# M621X.net
KiCad netlist of a schematic drawn in EAGLE
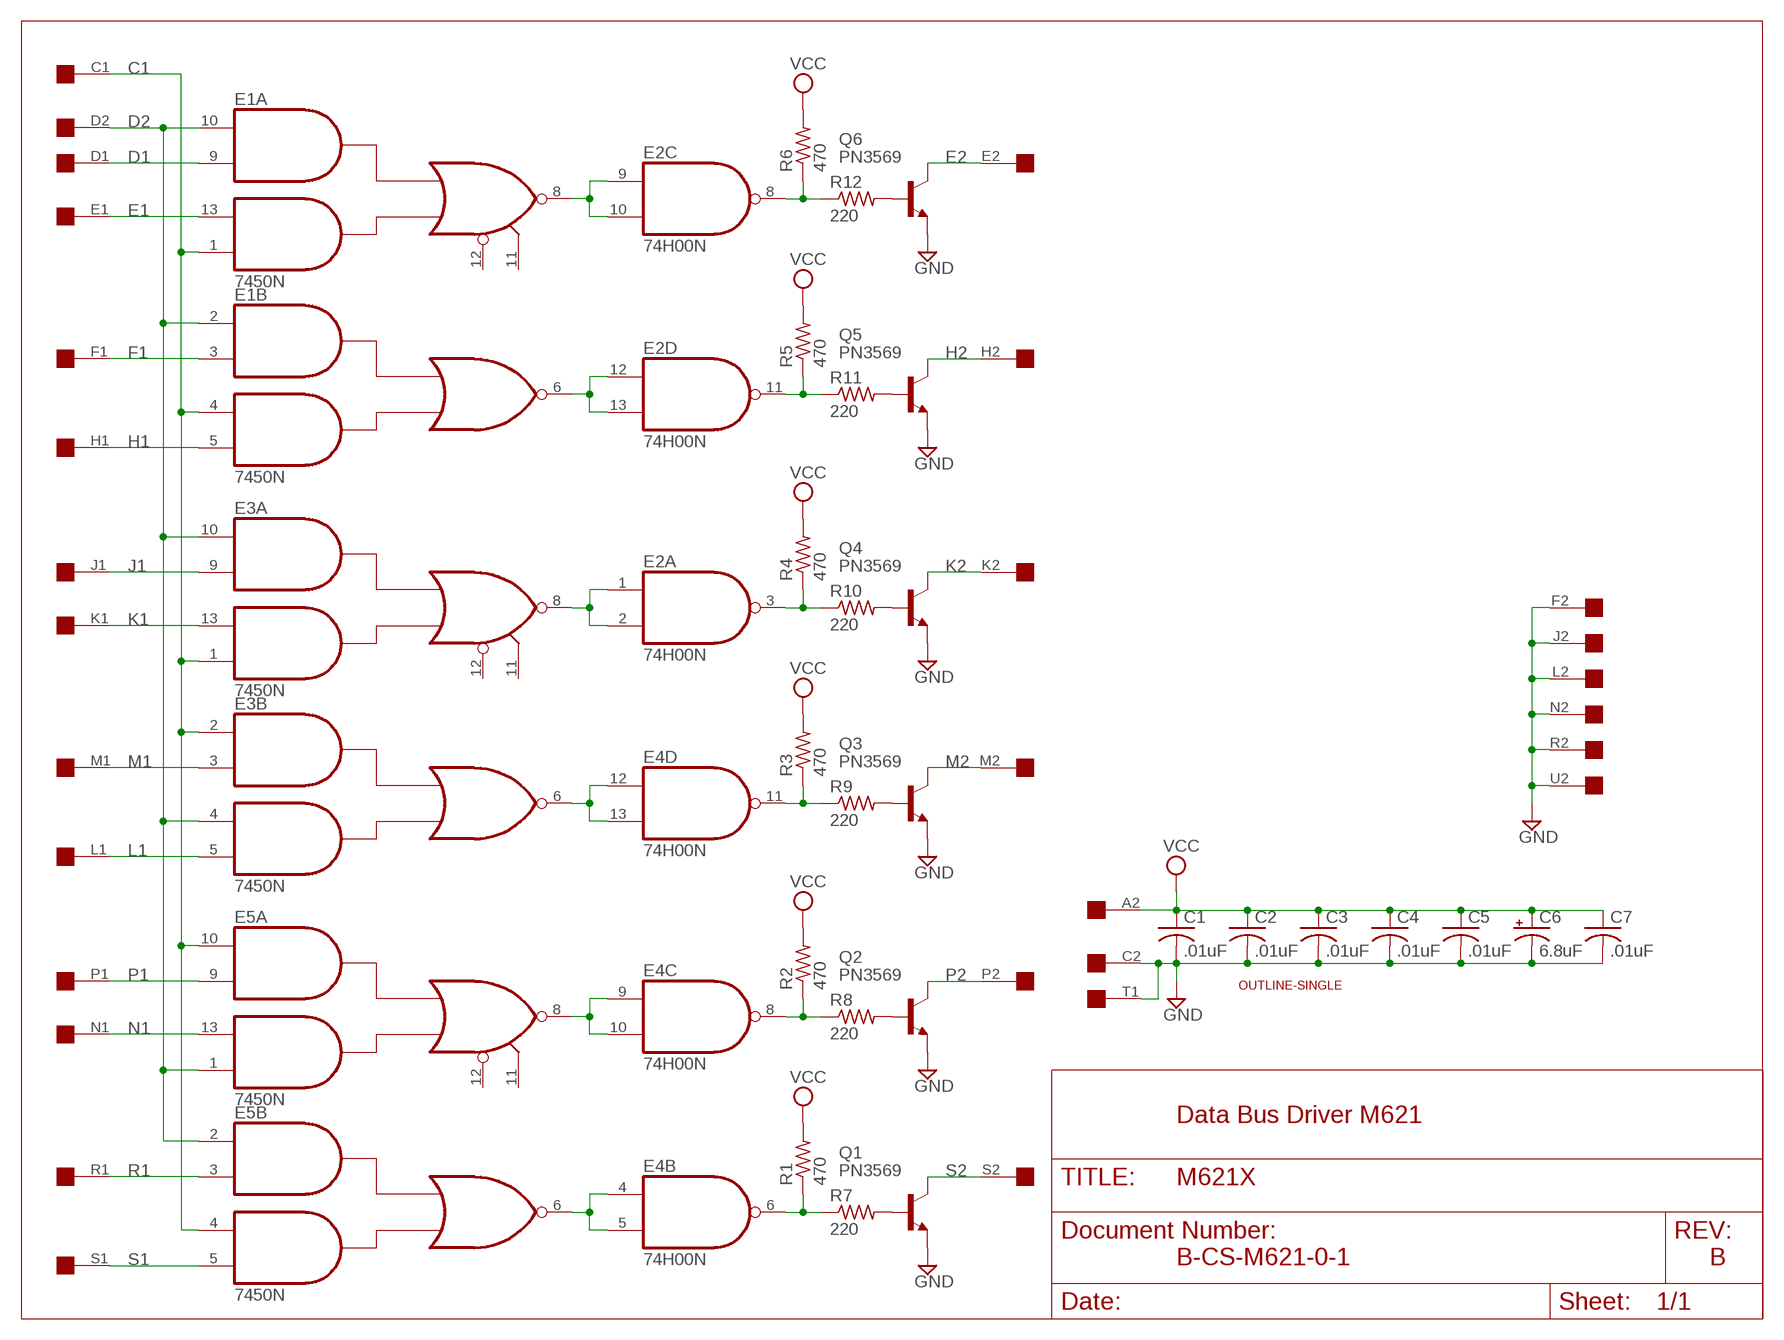
[diagram p0: schematic, sheet 1]

(export (version "E")
  (design (tool "Eeschema 10.0.6"))
  (components
    (comp (ref "C1")
      (value ".01uF")
      (footprint "eagle-import:C063-025X075")
      (libsource (lib "eagle-import") (part "C-US"))
    )
    (comp (ref "C2")
      (value ".01uF")
      (footprint "eagle-import:C063-025X075")
      (libsource (lib "eagle-import") (part "C-US"))
    )
    (comp (ref "C3")
      (value ".01uF")
      (footprint "eagle-import:C063-025X075")
      (libsource (lib "eagle-import") (part "C-US"))
    )
    (comp (ref "C4")
      (value ".01uF")
      (footprint "eagle-import:C063-025X075")
      (libsource (lib "eagle-import") (part "C-US"))
    )
    (comp (ref "C5")
      (value ".01uF")
      (footprint "eagle-import:C063-025X075")
      (libsource (lib "eagle-import") (part "C-US"))
    )
    (comp (ref "C6")
      (value "6.8uF")
      (footprint "eagle-import:E15-5")
      (libsource (lib "eagle-import") (part "CPOL-USE15-5AXIAL"))
    )
    (comp (ref "C7")
      (value ".01uF")
      (footprint "eagle-import:C063-025X075")
      (libsource (lib "eagle-import") (part "C-US"))
    )
    (comp (ref "E1")
      (value "7450N")
      (footprint "eagle-import:DIL14")
      (libsource (lib "eagle-import") (part "7450N"))
    )
    (comp (ref "E2")
      (value "74H00N")
      (footprint "eagle-import:DIL14")
      (libsource (lib "eagle-import") (part "7400NS"))
    )
    (comp (ref "E3")
      (value "7450N")
      (footprint "eagle-import:DIL14")
      (libsource (lib "eagle-import") (part "7450N"))
    )
    (comp (ref "E4")
      (value "74H00N")
      (footprint "eagle-import:DIL14")
      (libsource (lib "eagle-import") (part "7400NS"))
    )
    (comp (ref "E5")
      (value "7450N")
      (footprint "eagle-import:DIL14")
      (libsource (lib "eagle-import") (part "7450N"))
    )
    (comp (ref "Q1")
      (value "PN3569")
      (footprint "eagle-import:TO5")
      (libsource (lib "eagle-import") (part "-NPN-TO5"))
    )
    (comp (ref "Q2")
      (value "PN3569")
      (footprint "eagle-import:TO5")
      (libsource (lib "eagle-import") (part "-NPN-TO5"))
    )
    (comp (ref "Q3")
      (value "PN3569")
      (footprint "eagle-import:TO5")
      (libsource (lib "eagle-import") (part "-NPN-TO5"))
    )
    (comp (ref "Q4")
      (value "PN3569")
      (footprint "eagle-import:TO5")
      (libsource (lib "eagle-import") (part "-NPN-TO5"))
    )
    (comp (ref "Q5")
      (value "PN3569")
      (footprint "eagle-import:TO5")
      (libsource (lib "eagle-import") (part "-NPN-TO5"))
    )
    (comp (ref "Q6")
      (value "PN3569")
      (footprint "eagle-import:TO5")
      (libsource (lib "eagle-import") (part "-NPN-TO5"))
    )
    (comp (ref "R1")
      (value "470")
      (footprint "eagle-import:0207_10")
      (libsource (lib "eagle-import") (part "R-US_0207/10"))
    )
    (comp (ref "R2")
      (value "470")
      (footprint "eagle-import:0207_10")
      (libsource (lib "eagle-import") (part "R-US_0207/10"))
    )
    (comp (ref "R3")
      (value "470")
      (footprint "eagle-import:0207_10")
      (libsource (lib "eagle-import") (part "R-US_0207/10"))
    )
    (comp (ref "R4")
      (value "470")
      (footprint "eagle-import:0207_10")
      (libsource (lib "eagle-import") (part "R-US_0207/10"))
    )
    (comp (ref "R5")
      (value "470")
      (footprint "eagle-import:0207_10")
      (libsource (lib "eagle-import") (part "R-US_0207/10"))
    )
    (comp (ref "R6")
      (value "470")
      (footprint "eagle-import:0207_10")
      (libsource (lib "eagle-import") (part "R-US_0207/10"))
    )
    (comp (ref "R7")
      (value "220")
      (footprint "eagle-import:0207_10")
      (libsource (lib "eagle-import") (part "R-US_0207/10"))
    )
    (comp (ref "R8")
      (value "220")
      (footprint "eagle-import:0207_10")
      (libsource (lib "eagle-import") (part "R-US_0207/10"))
    )
    (comp (ref "R9")
      (value "220")
      (footprint "eagle-import:0207_10")
      (libsource (lib "eagle-import") (part "R-US_0207/10"))
    )
    (comp (ref "R10")
      (value "220")
      (footprint "eagle-import:0207_10")
      (libsource (lib "eagle-import") (part "R-US_0207/10"))
    )
    (comp (ref "R11")
      (value "220")
      (footprint "eagle-import:0207_10")
      (libsource (lib "eagle-import") (part "R-US_0207/10"))
    )
    (comp (ref "R12")
      (value "220")
      (footprint "eagle-import:0207_10")
      (libsource (lib "eagle-import") (part "R-US_0207/10"))
    )
    (comp (ref "U$1")
      (value "OUTLINE-SINGLE")
      (footprint "eagle-import:SINGLE")
      (libsource (lib "eagle-import") (part "OUTLINE-SINGLE"))
    )
    (comp (ref "U$2")
      (value "edge")
      (footprint "eagle-import:EDGE-CON2")
      (libsource (lib "eagle-import") (part "SINGLE"))
    )
  )
  (nets
    (net (code "1") (name "/C1") (class "Default")
      (node (ref "E1") (pin "1") (pinfunction "I4_1") (pintype "input"))
      (node (ref "E1") (pin "4") (pinfunction "I3_4") (pintype "input"))
      (node (ref "E3") (pin "1") (pinfunction "I4_1") (pintype "input"))
      (node (ref "E3") (pin "2") (pinfunction "I1_2") (pintype "input"))
      (node (ref "E5") (pin "10") (pinfunction "I1_10") (pintype "input"))
      (node (ref "E5") (pin "4") (pinfunction "I3_4") (pintype "input"))
      (node (ref "U$2") (pin "C1") (pinfunction "1_C1") (pintype "bidirectional"))
    )
    (net (code "2") (name "/D1") (class "Default")
      (node (ref "E1") (pin "9") (pinfunction "I2_9") (pintype "input"))
      (node (ref "U$2") (pin "D1") (pinfunction "1_D1") (pintype "bidirectional"))
    )
    (net (code "3") (name "/D2") (class "Default")
      (node (ref "E1") (pin "10") (pinfunction "I1_10") (pintype "input"))
      (node (ref "E1") (pin "2") (pinfunction "I1_2") (pintype "input"))
      (node (ref "E3") (pin "10") (pinfunction "I1_10") (pintype "input"))
      (node (ref "E3") (pin "4") (pinfunction "I3_4") (pintype "input"))
      (node (ref "E5") (pin "1") (pinfunction "I4_1") (pintype "input"))
      (node (ref "E5") (pin "2") (pinfunction "I1_2") (pintype "input"))
      (node (ref "U$2") (pin "D2") (pinfunction "1_D2") (pintype "bidirectional"))
    )
    (net (code "4") (name "/E1") (class "Default")
      (node (ref "E1") (pin "13") (pinfunction "I3_13") (pintype "input"))
      (node (ref "U$2") (pin "E1") (pinfunction "1_E1") (pintype "bidirectional"))
    )
    (net (code "5") (name "/E2") (class "Default")
      (node (ref "Q6") (pin "3") (pinfunction "C_3") (pintype "passive"))
      (node (ref "U$2") (pin "E2") (pinfunction "1_E2") (pintype "bidirectional"))
    )
    (net (code "6") (name "/F1") (class "Default")
      (node (ref "E1") (pin "3") (pinfunction "I2_3") (pintype "input"))
      (node (ref "U$2") (pin "F1") (pinfunction "1_F1") (pintype "bidirectional"))
    )
    (net (code "7") (name "/H1") (class "Default")
      (node (ref "E1") (pin "5") (pinfunction "I4_5") (pintype "input"))
      (node (ref "U$2") (pin "H1") (pinfunction "1_H1") (pintype "bidirectional"))
    )
    (net (code "8") (name "/H2") (class "Default")
      (node (ref "Q5") (pin "3") (pinfunction "C_3") (pintype "passive"))
      (node (ref "U$2") (pin "H2") (pinfunction "1_H2") (pintype "bidirectional"))
    )
    (net (code "9") (name "/J1") (class "Default")
      (node (ref "E3") (pin "9") (pinfunction "I2_9") (pintype "input"))
      (node (ref "U$2") (pin "J1") (pinfunction "1_J1") (pintype "bidirectional"))
    )
    (net (code "10") (name "/K1") (class "Default")
      (node (ref "E3") (pin "13") (pinfunction "I3_13") (pintype "input"))
      (node (ref "U$2") (pin "K1") (pinfunction "1_K1") (pintype "bidirectional"))
    )
    (net (code "11") (name "/K2") (class "Default")
      (node (ref "Q4") (pin "3") (pinfunction "C_3") (pintype "passive"))
      (node (ref "U$2") (pin "K2") (pinfunction "1_K2") (pintype "bidirectional"))
    )
    (net (code "12") (name "/L1") (class "Default")
      (node (ref "E3") (pin "5") (pinfunction "I4_5") (pintype "input"))
      (node (ref "U$2") (pin "L1") (pinfunction "1_L1") (pintype "bidirectional"))
    )
    (net (code "13") (name "/M1") (class "Default")
      (node (ref "E3") (pin "3") (pinfunction "I2_3") (pintype "input"))
      (node (ref "U$2") (pin "M1") (pinfunction "1_M1") (pintype "bidirectional"))
    )
    (net (code "14") (name "/M2") (class "Default")
      (node (ref "Q3") (pin "3") (pinfunction "C_3") (pintype "passive"))
      (node (ref "U$2") (pin "M2") (pinfunction "1_M2") (pintype "bidirectional"))
    )
    (net (code "15") (name "/N1") (class "Default")
      (node (ref "E5") (pin "13") (pinfunction "I3_13") (pintype "input"))
      (node (ref "U$2") (pin "N1") (pinfunction "1_N1") (pintype "bidirectional"))
    )
    (net (code "16") (name "/P1") (class "Default")
      (node (ref "E5") (pin "9") (pinfunction "I2_9") (pintype "input"))
      (node (ref "U$2") (pin "P1") (pinfunction "1_P1") (pintype "bidirectional"))
    )
    (net (code "17") (name "/P2") (class "Default")
      (node (ref "Q2") (pin "3") (pinfunction "C_3") (pintype "passive"))
      (node (ref "U$2") (pin "P2") (pinfunction "1_P2") (pintype "bidirectional"))
    )
    (net (code "18") (name "/R1") (class "Default")
      (node (ref "E5") (pin "3") (pinfunction "I2_3") (pintype "input"))
      (node (ref "U$2") (pin "R1") (pinfunction "1_R1") (pintype "bidirectional"))
    )
    (net (code "19") (name "/S1") (class "Default")
      (node (ref "E5") (pin "5") (pinfunction "I4_5") (pintype "input"))
      (node (ref "U$2") (pin "S1") (pinfunction "1_S1") (pintype "bidirectional"))
    )
    (net (code "20") (name "/S2") (class "Default")
      (node (ref "Q1") (pin "3") (pinfunction "C_3") (pintype "passive"))
      (node (ref "U$2") (pin "S2") (pinfunction "1_S2") (pintype "bidirectional"))
    )
    (net (code "21") (name "GND") (class "Default")
      (node (ref "C1") (pin "2") (pinfunction "2_2") (pintype "passive"))
      (node (ref "C2") (pin "2") (pinfunction "2_2") (pintype "passive"))
      (node (ref "C3") (pin "2") (pinfunction "2_2") (pintype "passive"))
      (node (ref "C4") (pin "2") (pinfunction "2_2") (pintype "passive"))
      (node (ref "C5") (pin "2") (pinfunction "2_2") (pintype "passive"))
      (node (ref "C6") (pin "-") (pinfunction "-_-") (pintype "passive"))
      (node (ref "C7") (pin "2") (pinfunction "2_2") (pintype "passive"))
      (node (ref "Q1") (pin "1") (pinfunction "E_1") (pintype "passive"))
      (node (ref "Q2") (pin "1") (pinfunction "E_1") (pintype "passive"))
      (node (ref "Q3") (pin "1") (pinfunction "E_1") (pintype "passive"))
      (node (ref "Q4") (pin "1") (pinfunction "E_1") (pintype "passive"))
      (node (ref "Q5") (pin "1") (pinfunction "E_1") (pintype "passive"))
      (node (ref "Q6") (pin "1") (pinfunction "E_1") (pintype "passive"))
      (node (ref "U$2") (pin "C2") (pinfunction "1_C2") (pintype "bidirectional"))
      (node (ref "U$2") (pin "F2") (pinfunction "1_F2") (pintype "bidirectional"))
      (node (ref "U$2") (pin "J2") (pinfunction "1_J2") (pintype "bidirectional"))
      (node (ref "U$2") (pin "L2") (pinfunction "1_L2") (pintype "bidirectional"))
      (node (ref "U$2") (pin "N2") (pinfunction "1_N2") (pintype "bidirectional"))
      (node (ref "U$2") (pin "R2") (pinfunction "1_R2") (pintype "bidirectional"))
      (node (ref "U$2") (pin "T1") (pinfunction "1_T1") (pintype "bidirectional"))
      (node (ref "U$2") (pin "U2") (pinfunction "1_U2") (pintype "bidirectional"))
    )
    (net (code "22") (name "Net-(E1A-O)") (class "Default")
      (node (ref "E1") (pin "8") (pinfunction "O_8") (pintype "output"))
      (node (ref "E2") (pin "10") (pinfunction "I1_10") (pintype "input"))
      (node (ref "E2") (pin "9") (pinfunction "I0_9") (pintype "input"))
    )
    (net (code "23") (name "Net-(E1B-O)") (class "Default")
      (node (ref "E1") (pin "6") (pinfunction "O_6") (pintype "output"))
      (node (ref "E2") (pin "12") (pinfunction "I0_12") (pintype "input"))
      (node (ref "E2") (pin "13") (pinfunction "I1_13") (pintype "input"))
    )
    (net (code "24") (name "Net-(E2A-I0)") (class "Default")
      (node (ref "E2") (pin "1") (pinfunction "I0_1") (pintype "input"))
      (node (ref "E2") (pin "2") (pinfunction "I1_2") (pintype "input"))
      (node (ref "E3") (pin "8") (pinfunction "O_8") (pintype "output"))
    )
    (net (code "25") (name "Net-(E2A-O)") (class "Default")
      (node (ref "E2") (pin "3") (pinfunction "O_3") (pintype "output"))
      (node (ref "R10") (pin "1") (pinfunction "1_1") (pintype "passive"))
      (node (ref "R4") (pin "1") (pinfunction "1_1") (pintype "passive"))
    )
    (net (code "26") (name "Net-(E2C-O)") (class "Default")
      (node (ref "E2") (pin "8") (pinfunction "O_8") (pintype "output"))
      (node (ref "R12") (pin "1") (pinfunction "1_1") (pintype "passive"))
      (node (ref "R6") (pin "1") (pinfunction "1_1") (pintype "passive"))
    )
    (net (code "27") (name "Net-(E2D-O)") (class "Default")
      (node (ref "E2") (pin "11") (pinfunction "O_11") (pintype "output"))
      (node (ref "R11") (pin "1") (pinfunction "1_1") (pintype "passive"))
      (node (ref "R5") (pin "1") (pinfunction "1_1") (pintype "passive"))
    )
    (net (code "28") (name "Net-(E3B-O)") (class "Default")
      (node (ref "E3") (pin "6") (pinfunction "O_6") (pintype "output"))
      (node (ref "E4") (pin "12") (pinfunction "I0_12") (pintype "input"))
      (node (ref "E4") (pin "13") (pinfunction "I1_13") (pintype "input"))
    )
    (net (code "29") (name "Net-(E4B-I0)") (class "Default")
      (node (ref "E4") (pin "4") (pinfunction "I0_4") (pintype "input"))
      (node (ref "E4") (pin "5") (pinfunction "I1_5") (pintype "input"))
      (node (ref "E5") (pin "6") (pinfunction "O_6") (pintype "output"))
    )
    (net (code "30") (name "Net-(E4B-O)") (class "Default")
      (node (ref "E4") (pin "6") (pinfunction "O_6") (pintype "output"))
      (node (ref "R1") (pin "1") (pinfunction "1_1") (pintype "passive"))
      (node (ref "R7") (pin "1") (pinfunction "1_1") (pintype "passive"))
    )
    (net (code "31") (name "Net-(E4C-I0)") (class "Default")
      (node (ref "E4") (pin "10") (pinfunction "I1_10") (pintype "input"))
      (node (ref "E4") (pin "9") (pinfunction "I0_9") (pintype "input"))
      (node (ref "E5") (pin "8") (pinfunction "O_8") (pintype "output"))
    )
    (net (code "32") (name "Net-(E4C-O)") (class "Default")
      (node (ref "E4") (pin "8") (pinfunction "O_8") (pintype "output"))
      (node (ref "R2") (pin "1") (pinfunction "1_1") (pintype "passive"))
      (node (ref "R8") (pin "1") (pinfunction "1_1") (pintype "passive"))
    )
    (net (code "33") (name "Net-(E4D-O)") (class "Default")
      (node (ref "E4") (pin "11") (pinfunction "O_11") (pintype "output"))
      (node (ref "R3") (pin "1") (pinfunction "1_1") (pintype "passive"))
      (node (ref "R9") (pin "1") (pinfunction "1_1") (pintype "passive"))
    )
    (net (code "34") (name "Net-(Q1-B)") (class "Default")
      (node (ref "Q1") (pin "2") (pinfunction "B_2") (pintype "passive"))
      (node (ref "R7") (pin "2") (pinfunction "2_2") (pintype "passive"))
    )
    (net (code "35") (name "Net-(Q2-B)") (class "Default")
      (node (ref "Q2") (pin "2") (pinfunction "B_2") (pintype "passive"))
      (node (ref "R8") (pin "2") (pinfunction "2_2") (pintype "passive"))
    )
    (net (code "36") (name "Net-(Q3-B)") (class "Default")
      (node (ref "Q3") (pin "2") (pinfunction "B_2") (pintype "passive"))
      (node (ref "R9") (pin "2") (pinfunction "2_2") (pintype "passive"))
    )
    (net (code "37") (name "Net-(Q4-B)") (class "Default")
      (node (ref "Q4") (pin "2") (pinfunction "B_2") (pintype "passive"))
      (node (ref "R10") (pin "2") (pinfunction "2_2") (pintype "passive"))
    )
    (net (code "38") (name "Net-(Q5-B)") (class "Default")
      (node (ref "Q5") (pin "2") (pinfunction "B_2") (pintype "passive"))
      (node (ref "R11") (pin "2") (pinfunction "2_2") (pintype "passive"))
    )
    (net (code "39") (name "Net-(Q6-B)") (class "Default")
      (node (ref "Q6") (pin "2") (pinfunction "B_2") (pintype "passive"))
      (node (ref "R12") (pin "2") (pinfunction "2_2") (pintype "passive"))
    )
    (net (code "40") (name "VCC") (class "Default")
      (node (ref "C1") (pin "1") (pinfunction "1_1") (pintype "passive"))
      (node (ref "C2") (pin "1") (pinfunction "1_1") (pintype "passive"))
      (node (ref "C3") (pin "1") (pinfunction "1_1") (pintype "passive"))
      (node (ref "C4") (pin "1") (pinfunction "1_1") (pintype "passive"))
      (node (ref "C5") (pin "1") (pinfunction "1_1") (pintype "passive"))
      (node (ref "C6") (pin "+") (pinfunction "+_+") (pintype "passive"))
      (node (ref "C7") (pin "1") (pinfunction "1_1") (pintype "passive"))
      (node (ref "R1") (pin "2") (pinfunction "2_2") (pintype "passive"))
      (node (ref "R2") (pin "2") (pinfunction "2_2") (pintype "passive"))
      (node (ref "R3") (pin "2") (pinfunction "2_2") (pintype "passive"))
      (node (ref "R4") (pin "2") (pinfunction "2_2") (pintype "passive"))
      (node (ref "R5") (pin "2") (pinfunction "2_2") (pintype "passive"))
      (node (ref "R6") (pin "2") (pinfunction "2_2") (pintype "passive"))
      (node (ref "U$2") (pin "A2") (pinfunction "1_A2") (pintype "bidirectional"))
    )
    (net (code "41") (name "unconnected-(E1A-I5-Pad12)") (class "Default")
      (node (ref "E1") (pin "12") (pinfunction "I5_12") (pintype "passive"))
    )
    (net (code "42") (name "unconnected-(E1A-I6-Pad11)") (class "Default")
      (node (ref "E1") (pin "11") (pinfunction "I6_11") (pintype "passive"))
    )
    (net (code "43") (name "unconnected-(E3A-I5-Pad12)") (class "Default")
      (node (ref "E3") (pin "12") (pinfunction "I5_12") (pintype "passive"))
    )
    (net (code "44") (name "unconnected-(E3A-I6-Pad11)") (class "Default")
      (node (ref "E3") (pin "11") (pinfunction "I6_11") (pintype "passive"))
    )
    (net (code "45") (name "unconnected-(E5A-I5-Pad12)") (class "Default")
      (node (ref "E5") (pin "12") (pinfunction "I5_12") (pintype "passive"))
    )
    (net (code "46") (name "unconnected-(E5A-I6-Pad11)") (class "Default")
      (node (ref "E5") (pin "11") (pinfunction "I6_11") (pintype "passive"))
    )
  )
)
